# morseovka.net
KiCad netlist of a schematic drawn in EAGLE
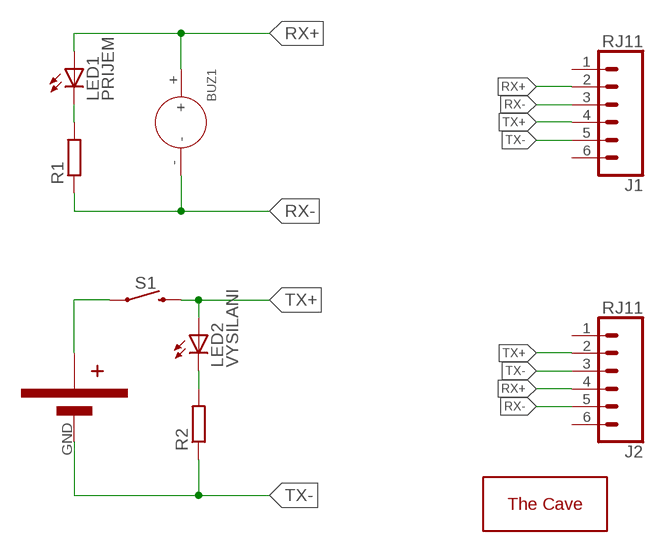
[diagram p0: schematic, sheet 1]

(export (version "E")
  (design (tool "Eeschema 10.0.6"))
  (components
    (comp (ref "BUZ1")
      (value "DIP-BUZZER-3V(KS-12065D03YA)")
      (footprint "eagle-import:BZ2-7.6-D12.0XH6.5MM")
      (fields (field (name "MPN") "KS-12065D03YA"))
      (libsource (lib "eagle-import") (part "DIP-BUZZER-3V(KS-12065D03YA)"))
    )
    (comp (ref "J1")
      (value "RJ11")
      (footprint "eagle-import:RJ11-6")
      (libsource (lib "eagle-import") (part "RJ11-6"))
    )
    (comp (ref "J2")
      (value "RJ11")
      (footprint "eagle-import:RJ11-6")
      (libsource (lib "eagle-import") (part "RJ11-6"))
    )
    (comp (ref "LED1")
      (value "PRIJEM")
      (footprint "eagle-import:LED5MM")
      (libsource (lib "eagle-import") (part "LED5MM"))
    )
    (comp (ref "LED2")
      (value "VYSILANI")
      (footprint "eagle-import:LED5MM")
      (libsource (lib "eagle-import") (part "LED5MM"))
    )
    (comp (ref "R1")
      (value "R-EU_0207/7")
      (footprint "eagle-import:0207_7")
      (libsource (lib "eagle-import") (part "R-EU_0207/7"))
    )
    (comp (ref "R2")
      (value "R-EU_0207/7")
      (footprint "eagle-import:0207_7")
      (libsource (lib "eagle-import") (part "R-EU_0207/7"))
    )
    (comp (ref "S1")
      (value "MOMENTARY-SWITCH-SPST-PTH-12MM")
      (footprint "eagle-import:TACTILE_SWITCH_PTH_12MM")
      (libsource (lib "eagle-import") (part "MOMENTARY-SWITCH-SPST-PTH-12MM"))
    )
    (comp (ref "U$1")
      (value "CR2032HSMD")
      (footprint "eagle-import:CR2032H")
      (libsource (lib "eagle-import") (part "CR2032HSMD"))
    )
    (comp (ref "U$2")
      (value "THECAVE_LOGO_NEW_TOP")
      (footprint "eagle-import:NEW_LOGO_TOP")
      (libsource (lib "eagle-import") (part "THECAVE_LOGO_NEW_TOP"))
    )
  )
  (nets
    (net (code "1") (name "Net-(LED1-C)") (class "Default")
      (node (ref "LED1") (pin "K") (pinfunction "C_K") (pintype "passive"))
      (node (ref "R1") (pin "2") (pinfunction "2_2") (pintype "passive"))
    )
    (net (code "2") (name "Net-(LED2-C)") (class "Default")
      (node (ref "LED2") (pin "K") (pinfunction "C_K") (pintype "passive"))
      (node (ref "R2") (pin "2") (pinfunction "2_2") (pintype "passive"))
    )
    (net (code "3") (name "Net-(S1-Pad1)") (class "Default")
      (node (ref "S1") (pin "1") (pinfunction "1_1") (pintype "passive"))
      (node (ref "U$1") (pin "VCC.1") (pinfunction "VCC_VCC.1") (pintype "power_in"))
      (node (ref "U$1") (pin "VCC.2") (pinfunction "VCC_VCC.2") (pintype "power_in"))
    )
    (net (code "4") (name "RX+") (class "Default")
      (node (ref "BUZ1") (pin "+") (pinfunction "+_+") (pintype "bidirectional"))
      (node (ref "J1") (pin "2") (pinfunction "2_2") (pintype "passive"))
      (node (ref "J2") (pin "4") (pinfunction "4_4") (pintype "passive"))
      (node (ref "LED1") (pin "A") (pinfunction "A_A") (pintype "passive"))
    )
    (net (code "5") (name "RX-") (class "Default")
      (node (ref "BUZ1") (pin "-") (pinfunction "-_-") (pintype "bidirectional"))
      (node (ref "J1") (pin "3") (pinfunction "3_3") (pintype "passive"))
      (node (ref "J2") (pin "5") (pinfunction "5_5") (pintype "passive"))
      (node (ref "R1") (pin "1") (pinfunction "1_1") (pintype "passive"))
    )
    (net (code "6") (name "TX+") (class "Default")
      (node (ref "J1") (pin "4") (pinfunction "4_4") (pintype "passive"))
      (node (ref "J2") (pin "2") (pinfunction "2_2") (pintype "passive"))
      (node (ref "LED2") (pin "A") (pinfunction "A_A") (pintype "passive"))
      (node (ref "S1") (pin "3") (pinfunction "2_3") (pintype "passive"))
    )
    (net (code "7") (name "TX-") (class "Default")
      (node (ref "J1") (pin "5") (pinfunction "5_5") (pintype "passive"))
      (node (ref "J2") (pin "3") (pinfunction "3_3") (pintype "passive"))
      (node (ref "R2") (pin "1") (pinfunction "1_1") (pintype "passive"))
      (node (ref "U$1") (pin "GND") (pinfunction "GND_GND") (pintype "power_in"))
    )
    (net (code "8") (name "unconnected-(J1-Pad1)") (class "Default")
      (node (ref "J1") (pin "1") (pinfunction "1_1") (pintype "passive"))
    )
    (net (code "9") (name "unconnected-(J1-Pad6)") (class "Default")
      (node (ref "J1") (pin "6") (pinfunction "6_6") (pintype "passive"))
    )
    (net (code "10") (name "unconnected-(J2-Pad1)") (class "Default")
      (node (ref "J2") (pin "1") (pinfunction "1_1") (pintype "passive"))
    )
    (net (code "11") (name "unconnected-(J2-Pad6)") (class "Default")
      (node (ref "J2") (pin "6") (pinfunction "6_6") (pintype "passive"))
    )
  )
)
